# can_transciever_dualvolt_isolated.net
KiCad netlist of a schematic drawn in Altium Designer
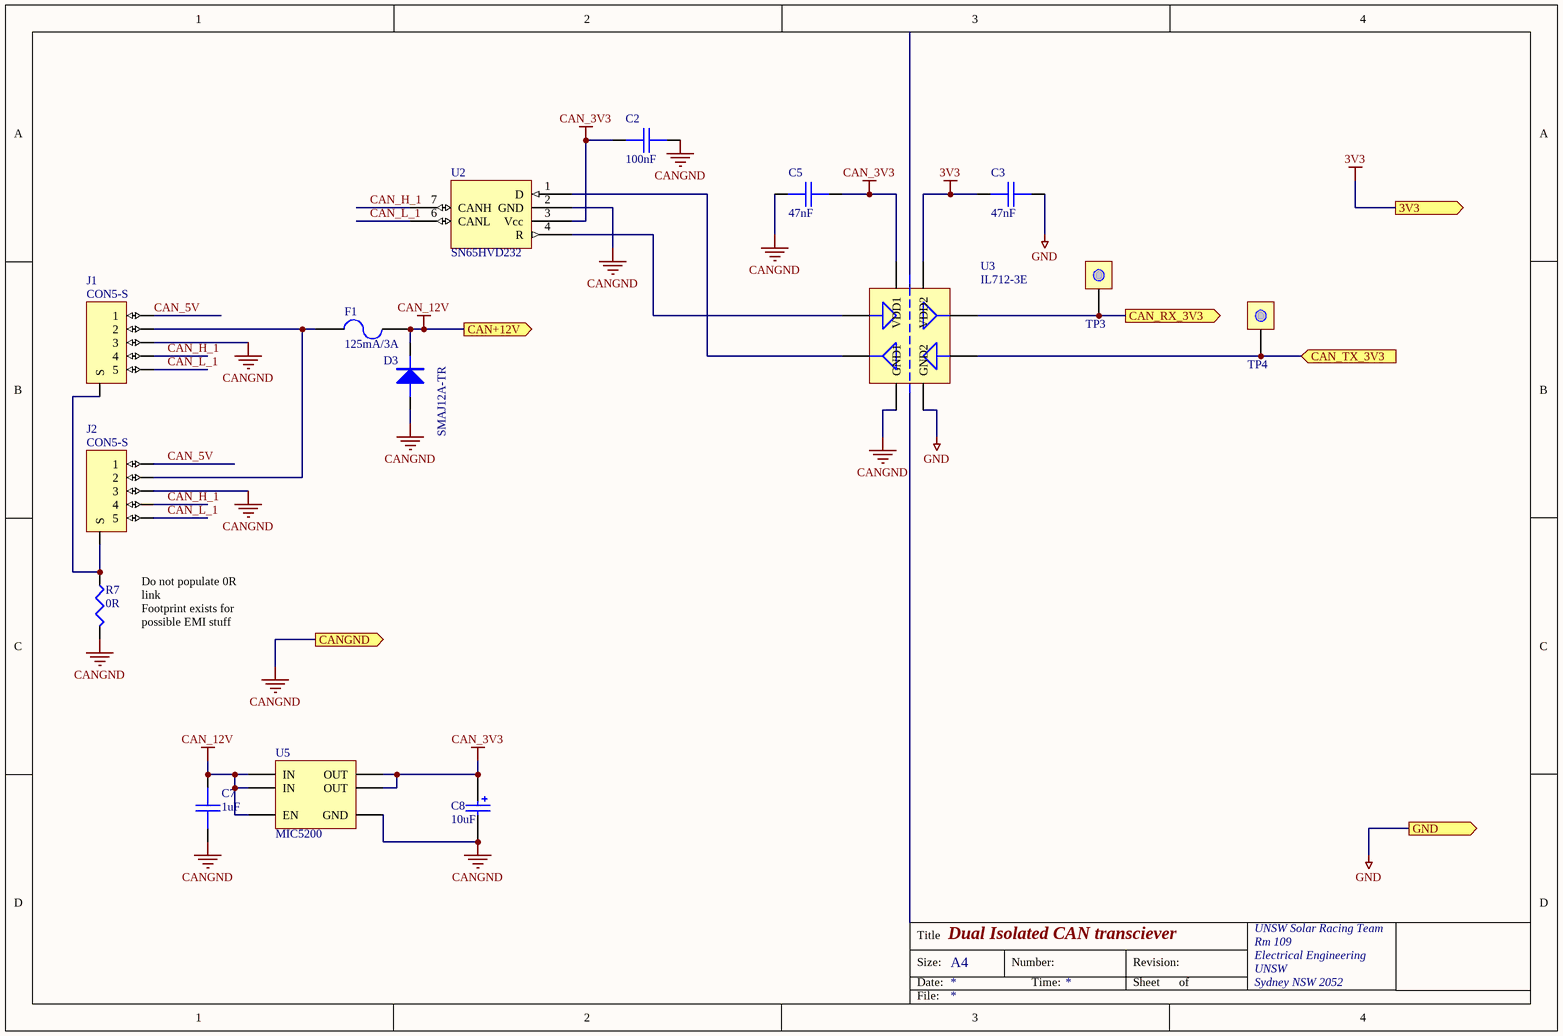
[diagram p0: can_transciever_dualvolt_isolated.SchDoc]

(export (version "E")
  (design (tool "Eeschema 10.0.6"))
  (components
    (comp (ref "C2")
      (value "100nF")
      (footprint "0603")
      (description "Capacitor")
      (libsource (lib "RCLDQ") (part "CAP"))
    )
    (comp (ref "C3")
      (value "47nF")
      (footprint "0603")
      (description "Capacitor")
      (libsource (lib "RCLDQ") (part "CAP"))
    )
    (comp (ref "C5")
      (value "47nF")
      (footprint "0603")
      (description "Capacitor")
      (libsource (lib "RCLDQ") (part "CAP"))
    )
    (comp (ref "C7")
      (value "1uF")
      (footprint "0805")
      (description "Capacitor")
      (libsource (lib "RCLDQ") (part "CAP"))
    )
    (comp (ref "C8")
      (value "10uF")
      (footprint "MCCT-CASEA")
      (description "Polarized Capacitor (Surface Mount)")
      (libsource (lib "RCLDQ") (part "CAP POL3"))
    )
    (comp (ref "D3")
      (value "SMAJ12A-TR")
      (footprint "SMA")
      (description "12V TVS Diode")
      (libsource (lib "RCLDQ") (part "DIODE"))
    )
    (comp (ref "F1")
      (value "125mA/3A")
      (footprint "LITTELFUSE-154")
      (description "Fuse")
      (libsource (lib "*") (part "FUSE2"))
    )
    (comp (ref "J1")
      (value "CON5-S")
      (footprint "TRIAD5F")
      (description "Connector, 2 pin, with shield @ S")
      (libsource (lib "Connectors") (part "CON5-S"))
    )
    (comp (ref "J2")
      (value "CON5-S")
      (footprint "TRIAD5F")
      (description "Connector, 2 pin, with shield @ S")
      (libsource (lib "Connectors") (part "CON5-S"))
    )
    (comp (ref "R7")
      (value "0R")
      (footprint "1206")
      (description "Resistor")
      (libsource (lib "RCLDQ") (part "RES1"))
    )
    (comp (ref "TP3")
      (value "RX")
      (footprint "TESTPOINT")
      (description "TEST POINT")
      (libsource (lib "Miscellaneous") (part "TEST"))
    )
    (comp (ref "TP4")
      (value "TX")
      (footprint "TESTPOINT")
      (description "TEST POINT")
      (libsource (lib "Miscellaneous") (part "TEST"))
    )
    (comp (ref "U2")
      (value "SN65HVD232")
      (footprint "SO8")
      (description "3.3V CAN Transciever")
      (libsource (lib "CAN") (part "SN65HVD232"))
    )
    (comp (ref "U3")
      (value "IL712-3E")
      (footprint "SO8")
      (description "IL712 Optical Isolator")
      (libsource (lib "Optocouplers") (part "IL712"))
    )
    (comp (ref "U5")
      (value "MIC5200")
      (footprint "SO8")
      (description "MIC5200 - SO8")
      (libsource (lib "*") (part "MIC5200"))
    )
  )
  (nets
    (net (code "1") (name "/CAN_5V") (class "Default")
      (node (ref "J1") (pin "1") (pinfunction "1_1") (pintype "bidirectional"))
      (node (ref "J2") (pin "1") (pinfunction "1_1") (pintype "bidirectional"))
    )
    (net (code "2") (name "/CAN_H_1") (class "Default")
      (node (ref "J1") (pin "4") (pinfunction "4_4") (pintype "bidirectional"))
      (node (ref "J2") (pin "4") (pinfunction "4_4") (pintype "bidirectional"))
      (node (ref "U2") (pin "7") (pinfunction "CANH_7") (pintype "bidirectional"))
    )
    (net (code "3") (name "/CAN_L_1") (class "Default")
      (node (ref "J1") (pin "5") (pinfunction "5_5") (pintype "bidirectional"))
      (node (ref "J2") (pin "5") (pinfunction "5_5") (pintype "bidirectional"))
      (node (ref "U2") (pin "6") (pinfunction "CANL_6") (pintype "bidirectional"))
    )
    (net (code "4") (name "/CAN_RX_3V3") (class "Default")
      (node (ref "TP3") (pin "0") (pinfunction "TP_0") (pintype "passive"))
      (node (ref "U3") (pin "7") (pinfunction "OUT1_7") (pintype "passive"))
    )
    (net (code "5") (name "/CAN_TX_3V3") (class "Default")
      (node (ref "TP4") (pin "0") (pinfunction "TP_0") (pintype "passive"))
      (node (ref "U3") (pin "6") (pinfunction "IN2_6") (pintype "passive"))
    )
    (net (code "6") (name "3V3") (class "Default")
      (node (ref "C3") (pin "1") (pinfunction "1_1") (pintype "passive"))
      (node (ref "U3") (pin "8") (pinfunction "VDD2_8") (pintype "passive"))
    )
    (net (code "7") (name "CANGND") (class "Default")
      (node (ref "C2") (pin "2") (pinfunction "2_2") (pintype "passive"))
      (node (ref "C5") (pin "1") (pinfunction "1_1") (pintype "passive"))
      (node (ref "C7") (pin "2") (pinfunction "2_2") (pintype "passive"))
      (node (ref "C8") (pin "2") (pinfunction "2_2") (pintype "passive"))
      (node (ref "D3") (pin "A") (pinfunction "A_A") (pintype "passive"))
      (node (ref "J1") (pin "3") (pinfunction "3_3") (pintype "bidirectional"))
      (node (ref "J2") (pin "3") (pinfunction "3_3") (pintype "bidirectional"))
      (node (ref "R7") (pin "2") (pinfunction "2_2") (pintype "passive"))
      (node (ref "U2") (pin "2") (pinfunction "GND_2") (pintype "power_in"))
      (node (ref "U3") (pin "4") (pinfunction "GND1_4") (pintype "passive"))
      (node (ref "U5") (pin "4") (pinfunction "GND_4") (pintype "passive"))
    )
    (net (code "8") (name "CAN_3V3") (class "Default")
      (node (ref "C2") (pin "1") (pinfunction "1_1") (pintype "passive"))
      (node (ref "C5") (pin "2") (pinfunction "2_2") (pintype "passive"))
      (node (ref "C8") (pin "1") (pinfunction "1_1") (pintype "passive"))
      (node (ref "U2") (pin "3") (pinfunction "Vcc_3") (pintype "power_in"))
      (node (ref "U3") (pin "1") (pinfunction "VDD1_1") (pintype "passive"))
      (node (ref "U5") (pin "1") (pinfunction "OUT_1") (pintype "passive"))
      (node (ref "U5") (pin "2") (pinfunction "OUT_2") (pintype "passive"))
    )
    (net (code "9") (name "CAN_12V") (class "Default")
      (node (ref "C7") (pin "1") (pinfunction "1_1") (pintype "passive"))
      (node (ref "D3") (pin "K") (pinfunction "K_K") (pintype "passive"))
      (node (ref "F1") (pin "2") (pinfunction "2_2") (pintype "passive"))
      (node (ref "U5") (pin "5") (pinfunction "EN_5") (pintype "passive"))
      (node (ref "U5") (pin "7") (pinfunction "IN_7") (pintype "passive"))
      (node (ref "U5") (pin "8") (pinfunction "IN_8") (pintype "passive"))
    )
    (net (code "10") (name "GND") (class "Default")
      (node (ref "C3") (pin "2") (pinfunction "2_2") (pintype "passive"))
      (node (ref "U3") (pin "5") (pinfunction "GND2_5") (pintype "passive"))
    )
    (net (code "11") (name "Net-(F1-Pad1)") (class "Default")
      (node (ref "F1") (pin "1") (pinfunction "1_1") (pintype "passive"))
      (node (ref "J1") (pin "2") (pinfunction "2_2") (pintype "bidirectional"))
      (node (ref "J2") (pin "2") (pinfunction "2_2") (pintype "bidirectional"))
    )
    (net (code "12") (name "Net-(J1-S)") (class "Default")
      (node (ref "J1") (pin "0") (pinfunction "S_0") (pintype "bidirectional"))
      (node (ref "J2") (pin "0") (pinfunction "S_0") (pintype "bidirectional"))
      (node (ref "R7") (pin "1") (pinfunction "1_1") (pintype "passive"))
    )
    (net (code "13") (name "Net-(U2-D)") (class "Default")
      (node (ref "U2") (pin "1") (pinfunction "D_1") (pintype "input"))
      (node (ref "U3") (pin "3") (pinfunction "OUT2_3") (pintype "passive"))
    )
    (net (code "14") (name "Net-(U2-R)") (class "Default")
      (node (ref "U2") (pin "4") (pinfunction "R_4") (pintype "output"))
      (node (ref "U3") (pin "2") (pinfunction "IN1_2") (pintype "passive"))
    )
  )
)
